# expansion-sn76489-kempton-sd-rev6.net
KiCad netlist of a schematic drawn in EAGLE
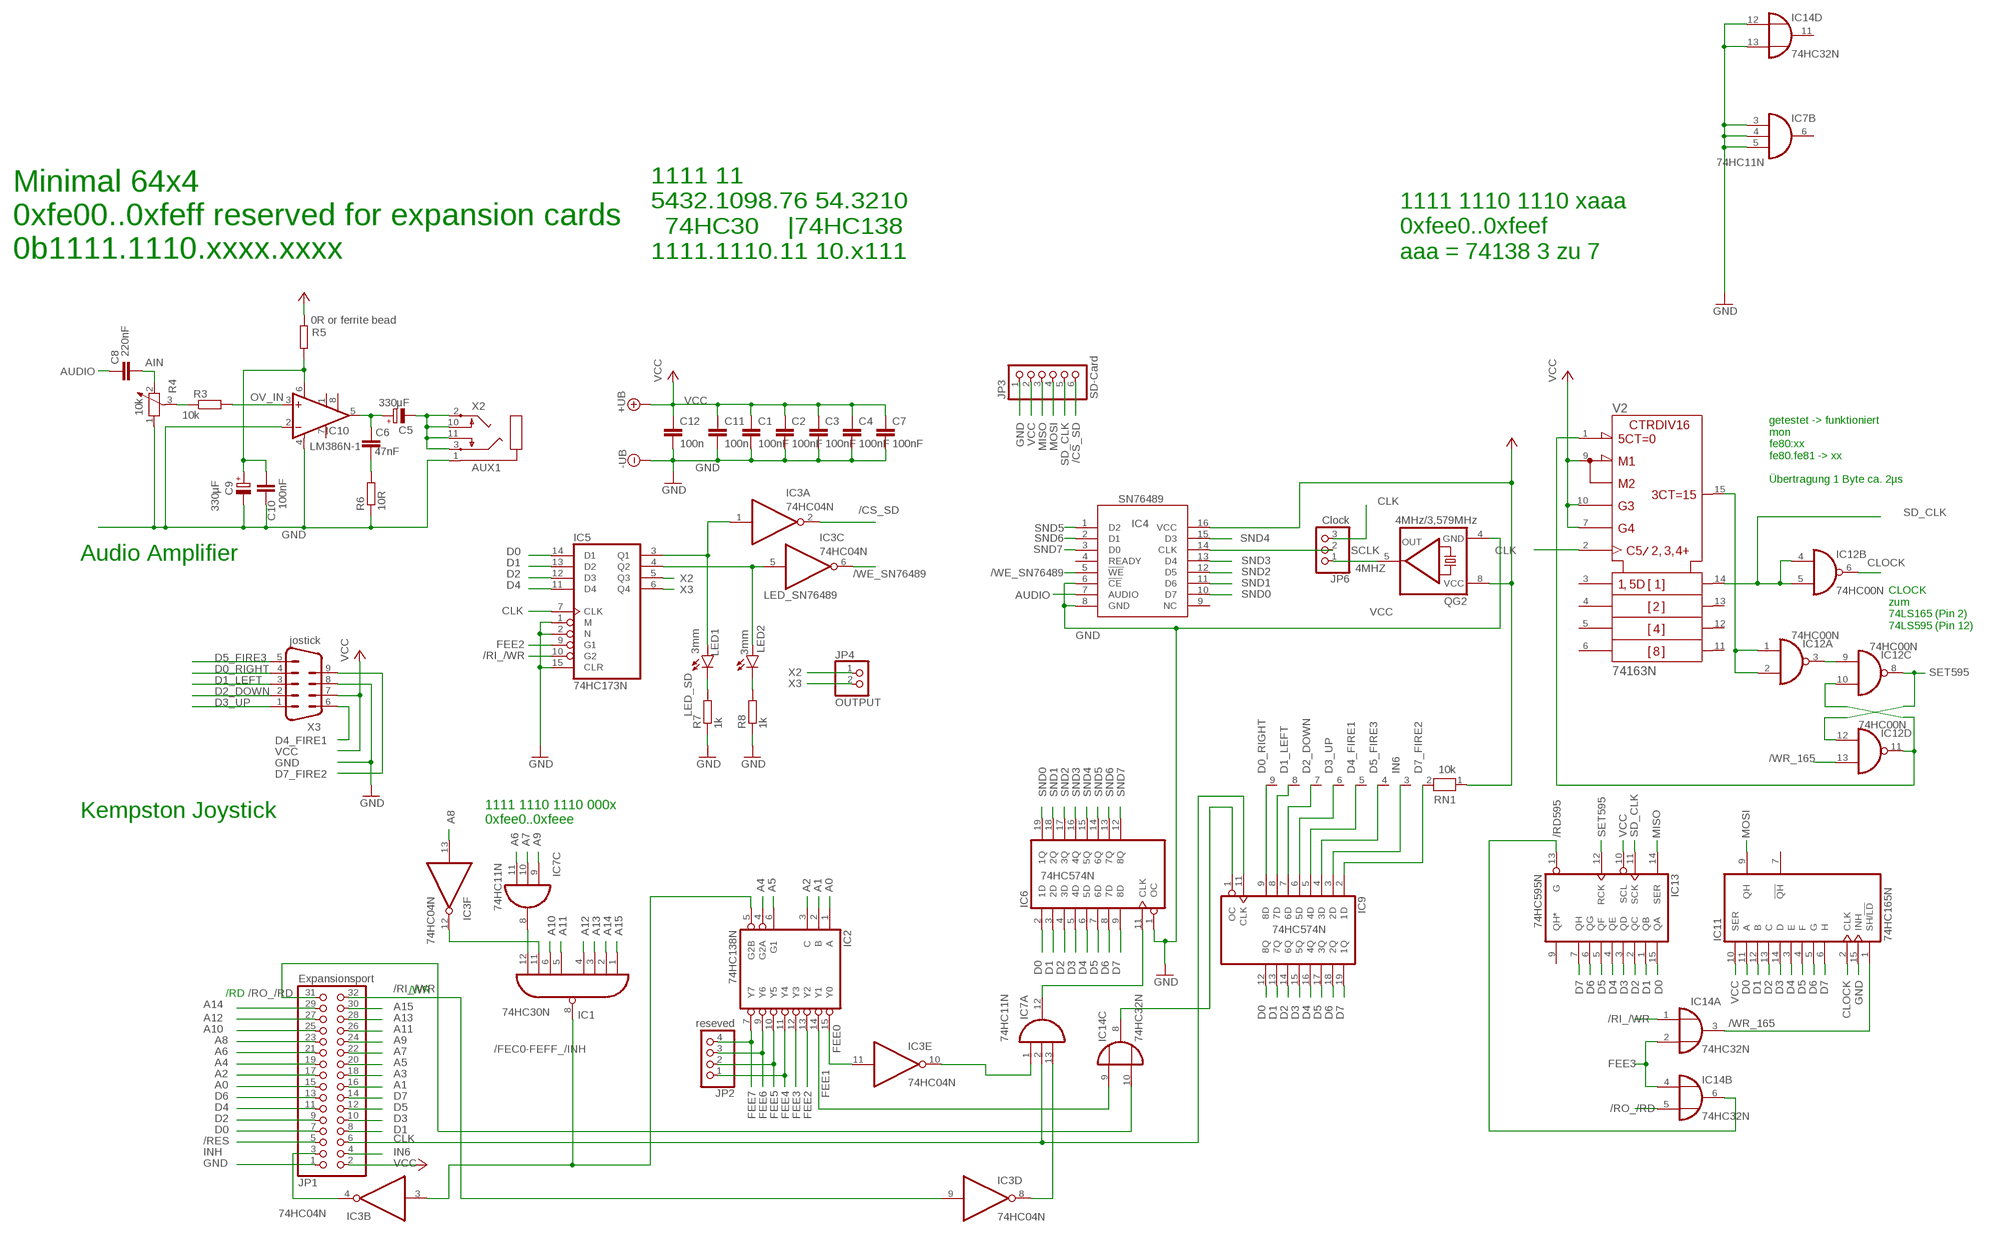
[diagram p0: schematic, sheet 1]

(export (version "E")
  (design (tool "Eeschema 10.0.6"))
  (components
    (comp (ref "C1")
      (value "100nF")
      (footprint "eagle-import:C050-025X075")
      (libsource (lib "eagle-import") (part "C-EU050-025X075"))
    )
    (comp (ref "C2")
      (value "100nF")
      (footprint "eagle-import:C050-025X075")
      (libsource (lib "eagle-import") (part "C-EU050-025X075"))
    )
    (comp (ref "C3")
      (value "100nF")
      (footprint "eagle-import:C050-025X075")
      (libsource (lib "eagle-import") (part "C-EU050-025X075"))
    )
    (comp (ref "C4")
      (value "100nF")
      (footprint "eagle-import:C050-025X075")
      (libsource (lib "eagle-import") (part "C-EU050-025X075"))
    )
    (comp (ref "C5")
      (value "330µF")
      (footprint "eagle-import:E2,5-7")
      (libsource (lib "eagle-import") (part "CPOL-EUE2.5-7"))
    )
    (comp (ref "C6")
      (value "47nF")
      (footprint "eagle-import:C050-025X075")
      (libsource (lib "eagle-import") (part "C-EU050-025X075"))
    )
    (comp (ref "C7")
      (value "100nF")
      (footprint "eagle-import:C050-025X075")
      (libsource (lib "eagle-import") (part "C-EU050-025X075"))
    )
    (comp (ref "C8")
      (value "220nF")
      (footprint "eagle-import:C050-025X075")
      (libsource (lib "eagle-import") (part "C-EU050-025X075"))
    )
    (comp (ref "C9")
      (value "330µF")
      (footprint "eagle-import:E2,5-7")
      (libsource (lib "eagle-import") (part "CPOL-EUE2.5-7"))
    )
    (comp (ref "C10")
      (value "100nF")
      (footprint "eagle-import:C050-025X075")
      (libsource (lib "eagle-import") (part "C-EU050-025X075"))
    )
    (comp (ref "C11")
      (value "100n")
      (footprint "eagle-import:C050-025X075")
      (libsource (lib "eagle-import") (part "C-EU050-025X075"))
    )
    (comp (ref "C12")
      (value "100n")
      (footprint "eagle-import:C050-025X075")
      (libsource (lib "eagle-import") (part "C-EU050-025X075"))
    )
    (comp (ref "IC1")
      (value "74HC30N")
      (footprint "eagle-import:DIL14")
      (libsource (lib "eagle-import") (part "7430NHC"))
    )
    (comp (ref "IC2")
      (value "74HC138N")
      (footprint "eagle-import:DIL16")
      (libsource (lib "eagle-import") (part "74138NHC"))
    )
    (comp (ref "IC3")
      (value "74HC04N")
      (footprint "eagle-import:DIL14")
      (libsource (lib "eagle-import") (part "7404NHC"))
    )
    (comp (ref "IC4")
      (value "SN76489")
      (footprint "eagle-import:ALEX-PARTS_DIL16")
      (libsource (lib "eagle-import") (part "ALEX-PARTS_SN76489AN"))
    )
    (comp (ref "IC5")
      (value "74HC173N")
      (footprint "eagle-import:DIL16")
      (libsource (lib "eagle-import") (part "74173NHC"))
    )
    (comp (ref "IC6")
      (value "74HC574N")
      (footprint "eagle-import:DIL20")
      (libsource (lib "eagle-import") (part "74574NHC"))
    )
    (comp (ref "IC7")
      (value "74HC11N")
      (footprint "eagle-import:DIL14")
      (libsource (lib "eagle-import") (part "7411NHC"))
    )
    (comp (ref "IC9")
      (value "74HC574N")
      (footprint "eagle-import:DIL20")
      (libsource (lib "eagle-import") (part "74574NHC"))
    )
    (comp (ref "IC10")
      (value "LM386N-1")
      (footprint "eagle-import:DIL08")
      (libsource (lib "eagle-import") (part "LM386?-N1"))
    )
    (comp (ref "IC11")
      (value "74HC165N")
      (footprint "eagle-import:DIL16")
      (libsource (lib "eagle-import") (part "74165NHC"))
    )
    (comp (ref "IC12")
      (value "74HC00N")
      (footprint "eagle-import:DIL14")
      (libsource (lib "eagle-import") (part "7400NHC"))
    )
    (comp (ref "IC13")
      (value "74HC595N")
      (footprint "eagle-import:DIL16")
      (libsource (lib "eagle-import") (part "74595NHC"))
    )
    (comp (ref "IC14")
      (value "74HC32N")
      (footprint "eagle-import:DIL14")
      (libsource (lib "eagle-import") (part "7432NHC"))
    )
    (comp (ref "JP1")
      (value "Expansionsport")
      (footprint "eagle-import:2X16")
      (libsource (lib "eagle-import") (part "PINHD-2X16"))
    )
    (comp (ref "JP2")
      (value "reseved")
      (footprint "eagle-import:1X04")
      (libsource (lib "eagle-import") (part "PINHD-1X4"))
    )
    (comp (ref "JP3")
      (value "SD-Card")
      (footprint "eagle-import:1X06")
      (libsource (lib "eagle-import") (part "PINHD-1X6"))
    )
    (comp (ref "JP4")
      (value "OUTPUT")
      (footprint "eagle-import:1X02")
      (libsource (lib "eagle-import") (part "PINHD-1X2"))
    )
    (comp (ref "JP6")
      (value "Clock")
      (footprint "eagle-import:1X03")
      (libsource (lib "eagle-import") (part "PINHD-1X3"))
    )
    (comp (ref "LED1")
      (value "3mm")
      (footprint "eagle-import:LED3MM")
      (libsource (lib "eagle-import") (part "LED3MM"))
    )
    (comp (ref "LED2")
      (value "3mm")
      (footprint "eagle-import:LED3MM")
      (libsource (lib "eagle-import") (part "LED3MM"))
    )
    (comp (ref "QG2")
      (value "4MHz/3,579MHz")
      (footprint "eagle-import:DIL08S")
      (libsource (lib "eagle-import") (part "QG5460"))
    )
    (comp (ref "R3")
      (value "10k")
      (footprint "eagle-import:0207_10")
      (libsource (lib "eagle-import") (part "R-EU_0207/10"))
    )
    (comp (ref "R4")
      (value "10k")
      (footprint "eagle-import:PT-10S")
      (libsource (lib "eagle-import") (part "POTENTIOMETER_PT-10S"))
    )
    (comp (ref "R5")
      (value "0R or ferrite bead")
      (footprint "eagle-import:0207_10")
      (libsource (lib "eagle-import") (part "R-EU_0207/10"))
    )
    (comp (ref "R6")
      (value "10R")
      (footprint "eagle-import:0207_10")
      (libsource (lib "eagle-import") (part "R-EU_0207/10"))
    )
    (comp (ref "R7")
      (value "1k")
      (footprint "eagle-import:0207_2V")
      (libsource (lib "eagle-import") (part "R-EU_0207/2V"))
    )
    (comp (ref "R8")
      (value "1k")
      (footprint "eagle-import:0207_2V")
      (libsource (lib "eagle-import") (part "R-EU_0207/2V"))
    )
    (comp (ref "RN1")
      (value "10k")
      (footprint "eagle-import:RN-9")
      (libsource (lib "eagle-import") (part "RN08"))
    )
    (comp (ref "V2")
      (value "74163N")
      (footprint "eagle-import:DIL16")
      (libsource (lib "eagle-import") (part "74163N"))
    )
    (comp (ref "X2")
      (value "AUX1")
      (footprint "eagle-import:SJ1-352XN")
      (libsource (lib "eagle-import") (part "CON-SJ1-352XNSJ1-352XN"))
    )
    (comp (ref "X3")
      (value "jostick")
      (footprint "eagle-import:182-009-MALE")
      (libsource (lib "eagle-import") (part "M09-182"))
    )
  )
  (nets
    (net (code "1") (name "+UB") (class "Default")
      (node (ref "C1") (pin "1") (pinfunction "1_1") (pintype "passive"))
      (node (ref "C11") (pin "1") (pinfunction "1_1") (pintype "passive"))
      (node (ref "C12") (pin "1") (pinfunction "1_1") (pintype "passive"))
      (node (ref "C2") (pin "1") (pinfunction "1_1") (pintype "passive"))
      (node (ref "C3") (pin "1") (pinfunction "1_1") (pintype "passive"))
      (node (ref "C4") (pin "1") (pinfunction "1_1") (pintype "passive"))
      (node (ref "C7") (pin "1") (pinfunction "1_1") (pintype "passive"))
      (node (ref "IC11") (pin "10") (pinfunction "SER_10") (pintype "input"))
      (node (ref "IC13") (pin "10") (pinfunction "SCL_10") (pintype "input"))
      (node (ref "IC4") (pin "16") (pinfunction "VCC_16") (pintype "input"))
      (node (ref "JP1") (pin "2") (pinfunction "2_2") (pintype "passive"))
      (node (ref "JP3") (pin "2") (pinfunction "2_2") (pintype "passive"))
      (node (ref "QG2") (pin "8") (pinfunction "VCC_8") (pintype "power_in"))
      (node (ref "R5") (pin "2") (pinfunction "2_2") (pintype "passive"))
      (node (ref "RN1") (pin "1") (pinfunction "1_1") (pintype "passive"))
      (node (ref "V2") (pin "10") (pinfunction "ENT_10") (pintype "input"))
      (node (ref "V2") (pin "7") (pinfunction "ENP_7") (pintype "input"))
      (node (ref "V2") (pin "9") (pinfunction "~{LOAD}_9") (pintype "input"))
      (node (ref "X3") (pin "7") (pinfunction "7_7") (pintype "passive"))
    )
    (net (code "2") (name "-UB") (class "Default")
      (node (ref "C1") (pin "2") (pinfunction "2_2") (pintype "passive"))
      (node (ref "C10") (pin "2") (pinfunction "2_2") (pintype "passive"))
      (node (ref "C11") (pin "2") (pinfunction "2_2") (pintype "passive"))
      (node (ref "C12") (pin "2") (pinfunction "2_2") (pintype "passive"))
      (node (ref "C2") (pin "2") (pinfunction "2_2") (pintype "passive"))
      (node (ref "C3") (pin "2") (pinfunction "2_2") (pintype "passive"))
      (node (ref "C4") (pin "2") (pinfunction "2_2") (pintype "passive"))
      (node (ref "C7") (pin "2") (pinfunction "2_2") (pintype "passive"))
      (node (ref "C9") (pin "-") (pinfunction "-_-") (pintype "passive"))
      (node (ref "IC10") (pin "2") (pinfunction "-IN_2") (pintype "input"))
      (node (ref "IC10") (pin "4") (pinfunction "GND_4") (pintype "power_in"))
      (node (ref "IC11") (pin "15") (pinfunction "INH_15") (pintype "input"))
      (node (ref "IC14") (pin "12") (pinfunction "I0_12") (pintype "input"))
      (node (ref "IC14") (pin "13") (pinfunction "I1_13") (pintype "input"))
      (node (ref "IC4") (pin "6") (pinfunction "~{CE}_6") (pintype "input"))
      (node (ref "IC4") (pin "8") (pinfunction "GND_8") (pintype "power_in"))
      (node (ref "IC5") (pin "1") (pinfunction "M_1") (pintype "input"))
      (node (ref "IC5") (pin "15") (pinfunction "CLR_15") (pintype "input"))
      (node (ref "IC5") (pin "2") (pinfunction "N_2") (pintype "input"))
      (node (ref "IC6") (pin "1") (pinfunction "OC_1") (pintype "input"))
      (node (ref "IC7") (pin "3") (pinfunction "I0_3") (pintype "input"))
      (node (ref "IC7") (pin "4") (pinfunction "I1_4") (pintype "input"))
      (node (ref "IC7") (pin "5") (pinfunction "I2_5") (pintype "input"))
      (node (ref "JP1") (pin "1") (pinfunction "1_1") (pintype "passive"))
      (node (ref "JP3") (pin "1") (pinfunction "1_1") (pintype "passive"))
      (node (ref "QG2") (pin "4") (pinfunction "GND_4") (pintype "power_in"))
      (node (ref "R4") (pin "1") (pinfunction "1_1") (pintype "passive"))
      (node (ref "R6") (pin "1") (pinfunction "1_1") (pintype "passive"))
      (node (ref "R7") (pin "1") (pinfunction "1_1") (pintype "passive"))
      (node (ref "R8") (pin "1") (pinfunction "1_1") (pintype "passive"))
      (node (ref "X2") (pin "1") (pinfunction "1_1") (pintype "passive"))
      (node (ref "X3") (pin "8") (pinfunction "8_8") (pintype "passive"))
    )
    (net (code "3") (name "/4MHZ") (class "Default")
      (node (ref "JP6") (pin "1") (pinfunction "1_1") (pintype "passive"))
      (node (ref "QG2") (pin "5") (pinfunction "OUT_5") (pintype "output"))
    )
    (net (code "4") (name "/A0") (class "Default")
      (node (ref "IC2") (pin "1") (pinfunction "A_1") (pintype "input"))
      (node (ref "JP1") (pin "15") (pinfunction "15_15") (pintype "passive"))
    )
    (net (code "5") (name "/A1") (class "Default")
      (node (ref "IC2") (pin "2") (pinfunction "B_2") (pintype "input"))
      (node (ref "JP1") (pin "16") (pinfunction "16_16") (pintype "passive"))
    )
    (net (code "6") (name "/A2") (class "Default")
      (node (ref "IC2") (pin "3") (pinfunction "C_3") (pintype "input"))
      (node (ref "JP1") (pin "17") (pinfunction "17_17") (pintype "passive"))
    )
    (net (code "7") (name "/A3") (class "Default")
      (node (ref "JP1") (pin "18") (pinfunction "18_18") (pintype "passive"))
    )
    (net (code "8") (name "/A4") (class "Default")
      (node (ref "IC2") (pin "4") (pinfunction "G2A_4") (pintype "input"))
      (node (ref "JP1") (pin "19") (pinfunction "19_19") (pintype "passive"))
    )
    (net (code "9") (name "/A5") (class "Default")
      (node (ref "IC2") (pin "6") (pinfunction "G1_6") (pintype "input"))
      (node (ref "JP1") (pin "20") (pinfunction "20_20") (pintype "passive"))
    )
    (net (code "10") (name "/A6") (class "Default")
      (node (ref "IC7") (pin "11") (pinfunction "I2_11") (pintype "input"))
      (node (ref "JP1") (pin "21") (pinfunction "21_21") (pintype "passive"))
    )
    (net (code "11") (name "/A7") (class "Default")
      (node (ref "IC7") (pin "10") (pinfunction "I1_10") (pintype "input"))
      (node (ref "JP1") (pin "22") (pinfunction "22_22") (pintype "passive"))
    )
    (net (code "12") (name "/A8") (class "Default")
      (node (ref "IC3") (pin "13") (pinfunction "I_13") (pintype "input"))
      (node (ref "JP1") (pin "23") (pinfunction "23_23") (pintype "passive"))
    )
    (net (code "13") (name "/A9") (class "Default")
      (node (ref "IC7") (pin "9") (pinfunction "I0_9") (pintype "input"))
      (node (ref "JP1") (pin "24") (pinfunction "24_24") (pintype "passive"))
    )
    (net (code "14") (name "/A10") (class "Default")
      (node (ref "IC1") (pin "6") (pinfunction "I5_6") (pintype "input"))
      (node (ref "JP1") (pin "25") (pinfunction "25_25") (pintype "passive"))
    )
    (net (code "15") (name "/A11") (class "Default")
      (node (ref "IC1") (pin "5") (pinfunction "I4_5") (pintype "input"))
      (node (ref "JP1") (pin "26") (pinfunction "26_26") (pintype "passive"))
    )
    (net (code "16") (name "/A12") (class "Default")
      (node (ref "IC1") (pin "4") (pinfunction "I3_4") (pintype "input"))
      (node (ref "JP1") (pin "27") (pinfunction "27_27") (pintype "passive"))
    )
    (net (code "17") (name "/A13") (class "Default")
      (node (ref "IC1") (pin "3") (pinfunction "I2_3") (pintype "input"))
      (node (ref "JP1") (pin "28") (pinfunction "28_28") (pintype "passive"))
    )
    (net (code "18") (name "/A14") (class "Default")
      (node (ref "IC1") (pin "2") (pinfunction "I1_2") (pintype "input"))
      (node (ref "JP1") (pin "29") (pinfunction "29_29") (pintype "passive"))
    )
    (net (code "19") (name "/A15") (class "Default")
      (node (ref "IC1") (pin "1") (pinfunction "I0_1") (pintype "input"))
      (node (ref "JP1") (pin "30") (pinfunction "30_30") (pintype "passive"))
    )
    (net (code "20") (name "/AIN") (class "Default")
      (node (ref "C8") (pin "2") (pinfunction "2_2") (pintype "passive"))
      (node (ref "R4") (pin "2") (pinfunction "2_2") (pintype "passive"))
    )
    (net (code "21") (name "/AUDIO") (class "Default")
      (node (ref "C8") (pin "1") (pinfunction "1_1") (pintype "passive"))
      (node (ref "IC4") (pin "7") (pinfunction "AUDIO_7") (pintype "output"))
    )
    (net (code "22") (name "/CLK") (class "Default")
      (node (ref "IC5") (pin "7") (pinfunction "CLK_7") (pintype "input"))
      (node (ref "IC7") (pin "2") (pinfunction "I1_2") (pintype "input"))
      (node (ref "IC9") (pin "11") (pinfunction "CLK_11") (pintype "input"))
      (node (ref "JP1") (pin "6") (pinfunction "6_6") (pintype "passive"))
      (node (ref "JP6") (pin "3") (pinfunction "3_3") (pintype "passive"))
      (node (ref "V2") (pin "2") (pinfunction "CLK_2") (pintype "input"))
    )
    (net (code "23") (name "/CLOCK") (class "Default")
      (node (ref "IC11") (pin "2") (pinfunction "CLK_2") (pintype "input"))
      (node (ref "IC12") (pin "6") (pinfunction "O_6") (pintype "output"))
    )
    (net (code "24") (name "/D0") (class "Default")
      (node (ref "IC11") (pin "11") (pinfunction "A_11") (pintype "input"))
      (node (ref "IC13") (pin "15") (pinfunction "QA_15") (pintype "tri_state"))
      (node (ref "IC5") (pin "14") (pinfunction "D1_14") (pintype "input"))
      (node (ref "IC6") (pin "2") (pinfunction "1D_2") (pintype "input"))
      (node (ref "IC9") (pin "12") (pinfunction "8Q_12") (pintype "tri_state"))
      (node (ref "JP1") (pin "7") (pinfunction "7_7") (pintype "passive"))
    )
    (net (code "25") (name "/D0_RIGHT") (class "Default")
      (node (ref "IC9") (pin "9") (pinfunction "8D_9") (pintype "input"))
      (node (ref "RN1") (pin "9") (pinfunction "9_9") (pintype "passive"))
      (node (ref "X3") (pin "4") (pinfunction "4_4") (pintype "passive"))
    )
    (net (code "26") (name "/D1") (class "Default")
      (node (ref "IC11") (pin "12") (pinfunction "B_12") (pintype "input"))
      (node (ref "IC13") (pin "1") (pinfunction "QB_1") (pintype "tri_state"))
      (node (ref "IC5") (pin "13") (pinfunction "D2_13") (pintype "input"))
      (node (ref "IC6") (pin "3") (pinfunction "2D_3") (pintype "input"))
      (node (ref "IC9") (pin "13") (pinfunction "7Q_13") (pintype "tri_state"))
      (node (ref "JP1") (pin "8") (pinfunction "8_8") (pintype "passive"))
    )
    (net (code "27") (name "/D1_LEFT") (class "Default")
      (node (ref "IC9") (pin "8") (pinfunction "7D_8") (pintype "input"))
      (node (ref "RN1") (pin "8") (pinfunction "8_8") (pintype "passive"))
      (node (ref "X3") (pin "3") (pinfunction "3_3") (pintype "passive"))
    )
    (net (code "28") (name "/D2") (class "Default")
      (node (ref "IC11") (pin "13") (pinfunction "C_13") (pintype "input"))
      (node (ref "IC13") (pin "2") (pinfunction "QC_2") (pintype "tri_state"))
      (node (ref "IC5") (pin "12") (pinfunction "D3_12") (pintype "input"))
      (node (ref "IC6") (pin "4") (pinfunction "3D_4") (pintype "input"))
      (node (ref "IC9") (pin "14") (pinfunction "6Q_14") (pintype "tri_state"))
      (node (ref "JP1") (pin "9") (pinfunction "9_9") (pintype "passive"))
    )
    (net (code "29") (name "/D2_DOWN") (class "Default")
      (node (ref "IC9") (pin "7") (pinfunction "6D_7") (pintype "input"))
      (node (ref "RN1") (pin "7") (pinfunction "7_7") (pintype "passive"))
      (node (ref "X3") (pin "2") (pinfunction "2_2") (pintype "passive"))
    )
    (net (code "30") (name "/D3") (class "Default")
      (node (ref "IC11") (pin "14") (pinfunction "D_14") (pintype "input"))
      (node (ref "IC13") (pin "3") (pinfunction "QD_3") (pintype "tri_state"))
      (node (ref "IC6") (pin "5") (pinfunction "4D_5") (pintype "input"))
      (node (ref "IC9") (pin "15") (pinfunction "5Q_15") (pintype "tri_state"))
      (node (ref "JP1") (pin "10") (pinfunction "10_10") (pintype "passive"))
    )
    (net (code "31") (name "/D3_UP") (class "Default")
      (node (ref "IC9") (pin "6") (pinfunction "5D_6") (pintype "input"))
      (node (ref "RN1") (pin "6") (pinfunction "6_6") (pintype "passive"))
      (node (ref "X3") (pin "1") (pinfunction "1_1") (pintype "passive"))
    )
    (net (code "32") (name "/D4") (class "Default")
      (node (ref "IC11") (pin "3") (pinfunction "E_3") (pintype "input"))
      (node (ref "IC13") (pin "4") (pinfunction "QE_4") (pintype "tri_state"))
      (node (ref "IC5") (pin "11") (pinfunction "D4_11") (pintype "input"))
      (node (ref "IC6") (pin "6") (pinfunction "5D_6") (pintype "input"))
      (node (ref "IC9") (pin "16") (pinfunction "4Q_16") (pintype "tri_state"))
      (node (ref "JP1") (pin "11") (pinfunction "11_11") (pintype "passive"))
    )
    (net (code "33") (name "/D4_FIRE1") (class "Default")
      (node (ref "IC9") (pin "5") (pinfunction "4D_5") (pintype "input"))
      (node (ref "RN1") (pin "5") (pinfunction "5_5") (pintype "passive"))
      (node (ref "X3") (pin "6") (pinfunction "6_6") (pintype "passive"))
    )
    (net (code "34") (name "/D5") (class "Default")
      (node (ref "IC11") (pin "4") (pinfunction "F_4") (pintype "input"))
      (node (ref "IC13") (pin "5") (pinfunction "QF_5") (pintype "tri_state"))
      (node (ref "IC6") (pin "7") (pinfunction "6D_7") (pintype "input"))
      (node (ref "IC9") (pin "17") (pinfunction "3Q_17") (pintype "tri_state"))
      (node (ref "JP1") (pin "12") (pinfunction "12_12") (pintype "passive"))
    )
    (net (code "35") (name "/D5_FIRE3") (class "Default")
      (node (ref "IC9") (pin "4") (pinfunction "3D_4") (pintype "input"))
      (node (ref "RN1") (pin "4") (pinfunction "4_4") (pintype "passive"))
      (node (ref "X3") (pin "5") (pinfunction "5_5") (pintype "passive"))
    )
    (net (code "36") (name "/D6") (class "Default")
      (node (ref "IC11") (pin "5") (pinfunction "G_5") (pintype "input"))
      (node (ref "IC13") (pin "6") (pinfunction "QG_6") (pintype "tri_state"))
      (node (ref "IC6") (pin "8") (pinfunction "7D_8") (pintype "input"))
      (node (ref "IC9") (pin "18") (pinfunction "2Q_18") (pintype "tri_state"))
      (node (ref "JP1") (pin "13") (pinfunction "13_13") (pintype "passive"))
    )
    (net (code "37") (name "/D7") (class "Default")
      (node (ref "IC11") (pin "6") (pinfunction "H_6") (pintype "input"))
      (node (ref "IC13") (pin "7") (pinfunction "QH_7") (pintype "tri_state"))
      (node (ref "IC6") (pin "9") (pinfunction "8D_9") (pintype "input"))
      (node (ref "IC9") (pin "19") (pinfunction "1Q_19") (pintype "tri_state"))
      (node (ref "JP1") (pin "14") (pinfunction "14_14") (pintype "passive"))
    )
    (net (code "38") (name "/D7_FIRE2") (class "Default")
      (node (ref "IC9") (pin "2") (pinfunction "1D_2") (pintype "input"))
      (node (ref "RN1") (pin "2") (pinfunction "2_2") (pintype "passive"))
      (node (ref "X3") (pin "9") (pinfunction "9_9") (pintype "passive"))
    )
    (net (code "39") (name "/FEE0") (class "Default")
      (node (ref "IC2") (pin "15") (pinfunction "Y0_15") (pintype "output"))
      (node (ref "IC3") (pin "11") (pinfunction "I_11") (pintype "input"))
    )
    (net (code "40") (name "/FEE1") (class "Default")
      (node (ref "IC14") (pin "9") (pinfunction "I0_9") (pintype "input"))
      (node (ref "IC2") (pin "14") (pinfunction "Y1_14") (pintype "output"))
    )
    (net (code "41") (name "/FEE2") (class "Default")
      (node (ref "IC2") (pin "13") (pinfunction "Y2_13") (pintype "output"))
      (node (ref "IC5") (pin "9") (pinfunction "G1_9") (pintype "input"))
    )
    (net (code "42") (name "/FEE3") (class "Default")
      (node (ref "IC14") (pin "2") (pinfunction "I1_2") (pintype "input"))
      (node (ref "IC14") (pin "4") (pinfunction "I0_4") (pintype "input"))
      (node (ref "IC2") (pin "12") (pinfunction "Y3_12") (pintype "output"))
    )
    (net (code "43") (name "/FEE4") (class "Default")
      (node (ref "IC2") (pin "11") (pinfunction "Y4_11") (pintype "output"))
      (node (ref "JP2") (pin "1") (pinfunction "1_1") (pintype "passive"))
    )
    (net (code "44") (name "/FEE5") (class "Default")
      (node (ref "IC2") (pin "10") (pinfunction "Y5_10") (pintype "output"))
      (node (ref "JP2") (pin "2") (pinfunction "2_2") (pintype "passive"))
    )
    (net (code "45") (name "/FEE6") (class "Default")
      (node (ref "IC2") (pin "9") (pinfunction "Y6_9") (pintype "output"))
      (node (ref "JP2") (pin "3") (pinfunction "3_3") (pintype "passive"))
    )
    (net (code "46") (name "/FEE7") (class "Default")
      (node (ref "IC2") (pin "7") (pinfunction "Y7_7") (pintype "output"))
      (node (ref "JP2") (pin "4") (pinfunction "4_4") (pintype "passive"))
    )
    (net (code "47") (name "/IN6") (class "Default")
      (node (ref "IC9") (pin "3") (pinfunction "2D_3") (pintype "input"))
      (node (ref "JP1") (pin "4") (pinfunction "4_4") (pintype "passive"))
      (node (ref "RN1") (pin "3") (pinfunction "3_3") (pintype "passive"))
    )
    (net (code "48") (name "/INH") (class "Default")
      (node (ref "IC3") (pin "4") (pinfunction "O_4") (pintype "output"))
      (node (ref "JP1") (pin "3") (pinfunction "3_3") (pintype "passive"))
    )
    (net (code "49") (name "/LED_SD") (class "Default")
      (node (ref "IC3") (pin "1") (pinfunction "I_1") (pintype "input"))
      (node (ref "IC5") (pin "3") (pinfunction "Q1_3") (pintype "tri_state"))
      (node (ref "LED1") (pin "A") (pinfunction "A_A") (pintype "passive"))
    )
    (net (code "50") (name "/LED_SN76489") (class "Default")
      (node (ref "IC3") (pin "5") (pinfunction "I_5") (pintype "input"))
      (node (ref "IC5") (pin "4") (pinfunction "Q2_4") (pintype "tri_state"))
      (node (ref "LED2") (pin "A") (pinfunction "A_A") (pintype "passive"))
    )
    (net (code "51") (name "/MISO") (class "Default")
      (node (ref "IC13") (pin "14") (pinfunction "SER_14") (pintype "input"))
      (node (ref "JP3") (pin "3") (pinfunction "3_3") (pintype "passive"))
    )
    (net (code "52") (name "/MOSI") (class "Default")
      (node (ref "IC11") (pin "9") (pinfunction "QH_9") (pintype "output"))
      (node (ref "JP3") (pin "4") (pinfunction "4_4") (pintype "passive"))
    )
    (net (code "53") (name "/OV_IN") (class "Default")
      (node (ref "IC10") (pin "3") (pinfunction "+IN_3") (pintype "input"))
      (node (ref "R3") (pin "2") (pinfunction "2_2") (pintype "passive"))
    )
    (net (code "54") (name "/SCLK") (class "Default")
      (node (ref "IC4") (pin "14") (pinfunction "CLK_14") (pintype "input"))
      (node (ref "JP6") (pin "2") (pinfunction "2_2") (pintype "passive"))
    )
    (net (code "55") (name "/SD_CLK") (class "Default")
      (node (ref "IC12") (pin "4") (pinfunction "I0_4") (pintype "input"))
      (node (ref "IC12") (pin "5") (pinfunction "I1_5") (pintype "input"))
      (node (ref "IC13") (pin "11") (pinfunction "SCK_11") (pintype "input"))
      (node (ref "JP3") (pin "5") (pinfunction "5_5") (pintype "passive"))
      (node (ref "V2") (pin "14") (pinfunction "QA_14") (pintype "output"))
    )
    (net (code "56") (name "/SET595") (class "Default")
      (node (ref "IC12") (pin "12") (pinfunction "I0_12") (pintype "input"))
      (node (ref "IC12") (pin "8") (pinfunction "O_8") (pintype "output"))
      (node (ref "IC13") (pin "12") (pinfunction "RCK_12") (pintype "input"))
    )
    (net (code "57") (name "/SND0") (class "Default")
      (node (ref "IC4") (pin "10") (pinfunction "D7_10") (pintype "input"))
      (node (ref "IC6") (pin "19") (pinfunction "1Q_19") (pintype "tri_state"))
    )
    (net (code "58") (name "/SND1") (class "Default")
      (node (ref "IC4") (pin "11") (pinfunction "D6_11") (pintype "input"))
      (node (ref "IC6") (pin "18") (pinfunction "2Q_18") (pintype "tri_state"))
    )
    (net (code "59") (name "/SND2") (class "Default")
      (node (ref "IC4") (pin "12") (pinfunction "D5_12") (pintype "input"))
      (node (ref "IC6") (pin "17") (pinfunction "3Q_17") (pintype "tri_state"))
    )
    (net (code "60") (name "/SND3") (class "Default")
      (node (ref "IC4") (pin "13") (pinfunction "D4_13") (pintype "input"))
      (node (ref "IC6") (pin "16") (pinfunction "4Q_16") (pintype "tri_state"))
    )
    (net (code "61") (name "/SND4") (class "Default")
      (node (ref "IC4") (pin "15") (pinfunction "D3_15") (pintype "input"))
      (node (ref "IC6") (pin "15") (pinfunction "5Q_15") (pintype "tri_state"))
    )
    (net (code "62") (name "/SND5") (class "Default")
      (node (ref "IC4") (pin "1") (pinfunction "D2_1") (pintype "input"))
      (node (ref "IC6") (pin "14") (pinfunction "6Q_14") (pintype "tri_state"))
    )
    (net (code "63") (name "/SND6") (class "Default")
      (node (ref "IC4") (pin "2") (pinfunction "D1_2") (pintype "input"))
      (node (ref "IC6") (pin "13") (pinfunction "7Q_13") (pintype "tri_state"))
    )
    (net (code "64") (name "/SND7") (class "Default")
      (node (ref "IC4") (pin "3") (pinfunction "D0_3") (pintype "input"))
      (node (ref "IC6") (pin "12") (pinfunction "8Q_12") (pintype "tri_state"))
    )
    (net (code "65") (name "/X2") (class "Default")
      (node (ref "IC5") (pin "5") (pinfunction "Q3_5") (pintype "tri_state"))
      (node (ref "JP4") (pin "1") (pinfunction "1_1") (pintype "passive"))
    )
    (net (code "66") (name "/X3") (class "Default")
      (node (ref "IC5") (pin "6") (pinfunction "Q4_6") (pintype "tri_state"))
      (node (ref "JP4") (pin "2") (pinfunction "2_2") (pintype "passive"))
    )
    (net (code "67") (name "/{slash}CS_SD") (class "Default")
      (node (ref "IC3") (pin "2") (pinfunction "O_2") (pintype "output"))
      (node (ref "JP3") (pin "6") (pinfunction "6_6") (pintype "passive"))
    )
    (net (code "68") (name "/{slash}FEC0-FEFF_{slash}INH") (class "Default")
      (node (ref "IC1") (pin "8") (pinfunction "O_8") (pintype "output"))
      (node (ref "IC2") (pin "5") (pinfunction "G2B_5") (pintype "input"))
      (node (ref "IC3") (pin "3") (pinfunction "I_3") (pintype "input"))
    )
    (net (code "69") (name "/{slash}RD595") (class "Default")
      (node (ref "IC13") (pin "13") (pinfunction "G_13") (pintype "input"))
      (node (ref "IC14") (pin "6") (pinfunction "O_6") (pintype "output"))
    )
    (net (code "70") (name "/{slash}RES") (class "Default")
      (node (ref "JP1") (pin "5") (pinfunction "5_5") (pintype "passive"))
    )
    (net (code "71") (name "/{slash}RI_{slash}WR") (class "Default")
      (node (ref "IC14") (pin "1") (pinfunction "I0_1") (pintype "input"))
      (node (ref "IC3") (pin "9") (pinfunction "I_9") (pintype "input"))
      (node (ref "IC5") (pin "10") (pinfunction "G2_10") (pintype "input"))
      (node (ref "JP1") (pin "32") (pinfunction "32_32") (pintype "passive"))
    )
    (net (code "72") (name "/{slash}RO_{slash}RD") (class "Default")
      (node (ref "IC14") (pin "10") (pinfunction "I1_10") (pintype "input"))
      (node (ref "IC14") (pin "5") (pinfunction "I1_5") (pintype "input"))
      (node (ref "JP1") (pin "31") (pinfunction "31_31") (pintype "passive"))
    )
    (net (code "73") (name "/{slash}WE_SN76489") (class "Default")
      (node (ref "IC3") (pin "6") (pinfunction "O_6") (pintype "output"))
      (node (ref "IC4") (pin "5") (pinfunction "~{WE}_5") (pintype "input"))
    )
    (net (code "74") (name "/{slash}WR_165") (class "Default")
      (node (ref "IC11") (pin "1") (pinfunction "SH/~{LD}_1") (pintype "input"))
      (node (ref "IC12") (pin "13") (pinfunction "I1_13") (pintype "input"))
      (node (ref "IC14") (pin "3") (pinfunction "O_3") (pintype "output"))
    )
    (net (code "75") (name "Net-(C5-Pad-)") (class "Default")
      (node (ref "C5") (pin "-") (pinfunction "-_-") (pintype "passive"))
      (node (ref "X2") (pin "10") (pinfunction "10_10") (pintype "passive"))
      (node (ref "X2") (pin "11") (pinfunction "11_11") (pintype "passive"))
      (node (ref "X2") (pin "2") (pinfunction "2_2") (pintype "passive"))
      (node (ref "X2") (pin "3") (pinfunction "3_3") (pintype "passive"))
    )
    (net (code "76") (name "Net-(C6-Pad2)") (class "Default")
      (node (ref "C6") (pin "2") (pinfunction "2_2") (pintype "passive"))
      (node (ref "R6") (pin "2") (pinfunction "2_2") (pintype "passive"))
    )
    (net (code "77") (name "Net-(IC1A-I6)") (class "Default")
      (node (ref "IC1") (pin "11") (pinfunction "I6_11") (pintype "input"))
      (node (ref "IC3") (pin "12") (pinfunction "O_12") (pintype "output"))
    )
    (net (code "78") (name "Net-(IC1A-I7)") (class "Default")
      (node (ref "IC1") (pin "12") (pinfunction "I7_12") (pintype "input"))
      (node (ref "IC7") (pin "8") (pinfunction "O_8") (pintype "output"))
    )
    (net (code "79") (name "Net-(IC3D-O)") (class "Default")
      (node (ref "IC3") (pin "8") (pinfunction "O_8") (pintype "output"))
      (node (ref "IC7") (pin "13") (pinfunction "I2_13") (pintype "input"))
    )
    (net (code "80") (name "Net-(IC3E-O)") (class "Default")
      (node (ref "IC3") (pin "10") (pinfunction "O_10") (pintype "output"))
      (node (ref "IC7") (pin "1") (pinfunction "I0_1") (pintype "input"))
    )
    (net (code "81") (name "Net-(IC6A-CLK)") (class "Default")
      (node (ref "IC6") (pin "11") (pinfunction "CLK_11") (pintype "input"))
      (node (ref "IC7") (pin "12") (pinfunction "O_12") (pintype "output"))
    )
    (net (code "82") (name "Net-(IC10-OUT)") (class "Default")
      (node (ref "C5") (pin "+") (pinfunction "+_+") (pintype "passive"))
      (node (ref "C6") (pin "1") (pinfunction "1_1") (pintype "passive"))
      (node (ref "IC10") (pin "5") (pinfunction "OUT_5") (pintype "output"))
    )
    (net (code "83") (name "Net-(IC10-VS)") (class "Default")
      (node (ref "C10") (pin "1") (pinfunction "1_1") (pintype "passive"))
      (node (ref "C9") (pin "+") (pinfunction "+_+") (pintype "passive"))
      (node (ref "IC10") (pin "6") (pinfunction "VS_6") (pintype "power_in"))
      (node (ref "R5") (pin "1") (pinfunction "1_1") (pintype "passive"))
    )
    (net (code "84") (name "Net-(IC12A-I0)") (class "Default")
      (node (ref "IC12") (pin "1") (pinfunction "I0_1") (pintype "input"))
      (node (ref "IC12") (pin "2") (pinfunction "I1_2") (pintype "input"))
      (node (ref "V2") (pin "15") (pinfunction "RCO_15") (pintype "output"))
    )
    (net (code "85") (name "Net-(IC12A-O)") (class "Default")
      (node (ref "IC12") (pin "3") (pinfunction "O_3") (pintype "output"))
      (node (ref "IC12") (pin "9") (pinfunction "I0_9") (pintype "input"))
    )
    (net (code "86") (name "Net-(IC12C-I1)") (class "Default")
      (node (ref "IC12") (pin "10") (pinfunction "I1_10") (pintype "input"))
      (node (ref "IC12") (pin "11") (pinfunction "O_11") (pintype "output"))
      (node (ref "V2") (pin "1") (pinfunction "~{CLR}_1") (pintype "input"))
    )
    (net (code "87") (name "Net-(IC14C-O)") (class "Default")
      (node (ref "IC14") (pin "8") (pinfunction "O_8") (pintype "output"))
      (node (ref "IC9") (pin "1") (pinfunction "OC_1") (pintype "input"))
    )
    (net (code "88") (name "Net-(LED1-C)") (class "Default")
      (node (ref "LED1") (pin "K") (pinfunction "C_K") (pintype "passive"))
      (node (ref "R7") (pin "2") (pinfunction "2_2") (pintype "passive"))
    )
    (net (code "89") (name "Net-(LED2-C)") (class "Default")
      (node (ref "LED2") (pin "K") (pinfunction "C_K") (pintype "passive"))
      (node (ref "R8") (pin "2") (pinfunction "2_2") (pintype "passive"))
    )
    (net (code "90") (name "Net-(R3-Pad1)") (class "Default")
      (node (ref "R3") (pin "1") (pinfunction "1_1") (pintype "passive"))
      (node (ref "R4") (pin "3") (pinfunction "3_3") (pintype "passive"))
    )
    (net (code "91") (name "unconnected-(IC4-NC-Pad9)") (class "Default")
      (node (ref "IC4") (pin "9") (pinfunction "NC_9") (pintype "no_connect"))
    )
    (net (code "92") (name "unconnected-(IC4-READY-Pad4)") (class "Default")
      (node (ref "IC4") (pin "4") (pinfunction "READY_4") (pintype "output"))
    )
    (net (code "93") (name "unconnected-(IC7B-O-Pad6)") (class "Default")
      (node (ref "IC7") (pin "6") (pinfunction "O_6") (pintype "output"))
    )
    (net (code "94") (name "unconnected-(IC10-BYPASS-Pad7)") (class "Default")
      (node (ref "IC10") (pin "7") (pinfunction "BYPASS_7") (pintype "passive"))
    )
    (net (code "95") (name "unconnected-(IC10-GAIN-Pad1)") (class "Default")
      (node (ref "IC10") (pin "1") (pinfunction "GAIN_1") (pintype "passive"))
    )
    (net (code "96") (name "unconnected-(IC10-GAIN-Pad8)") (class "Default")
      (node (ref "IC10") (pin "8") (pinfunction "GAIN_8") (pintype "passive"))
    )
    (net (code "97") (name "unconnected-(IC11A-~{QH}-Pad7)") (class "Default")
      (node (ref "IC11") (pin "7") (pinfunction "~{QH}_7") (pintype "output"))
    )
    (net (code "98") (name "unconnected-(IC13A-QH*-Pad9)") (class "Default")
      (node (ref "IC13") (pin "9") (pinfunction "QH*_9") (pintype "tri_state"))
    )
    (net (code "99") (name "unconnected-(IC14D-O-Pad11)") (class "Default")
      (node (ref "IC14") (pin "11") (pinfunction "O_11") (pintype "output"))
    )
    (net (code "100") (name "unconnected-(V2C-A-Pad3)") (class "Default")
      (node (ref "V2") (pin "3") (pinfunction "A_3") (pintype "input"))
    )
    (net (code "101") (name "unconnected-(V2C-B-Pad4)") (class "Default")
      (node (ref "V2") (pin "4") (pinfunction "B_4") (pintype "input"))
    )
    (net (code "102") (name "unconnected-(V2C-C-Pad5)") (class "Default")
      (node (ref "V2") (pin "5") (pinfunction "C_5") (pintype "input"))
    )
    (net (code "103") (name "unconnected-(V2C-D-Pad6)") (class "Default")
      (node (ref "V2") (pin "6") (pinfunction "D_6") (pintype "input"))
    )
    (net (code "104") (name "unconnected-(V2C-QB-Pad13)") (class "Default")
      (node (ref "V2") (pin "13") (pinfunction "QB_13") (pintype "output"))
    )
    (net (code "105") (name "unconnected-(V2C-QC-Pad12)") (class "Default")
      (node (ref "V2") (pin "12") (pinfunction "QC_12") (pintype "output"))
    )
    (net (code "106") (name "unconnected-(V2C-QD-Pad11)") (class "Default")
      (node (ref "V2") (pin "11") (pinfunction "QD_11") (pintype "output"))
    )
  )
)
